# HDMI_INTERFACE.net
KiCad netlist of a schematic drawn in Altium Designer
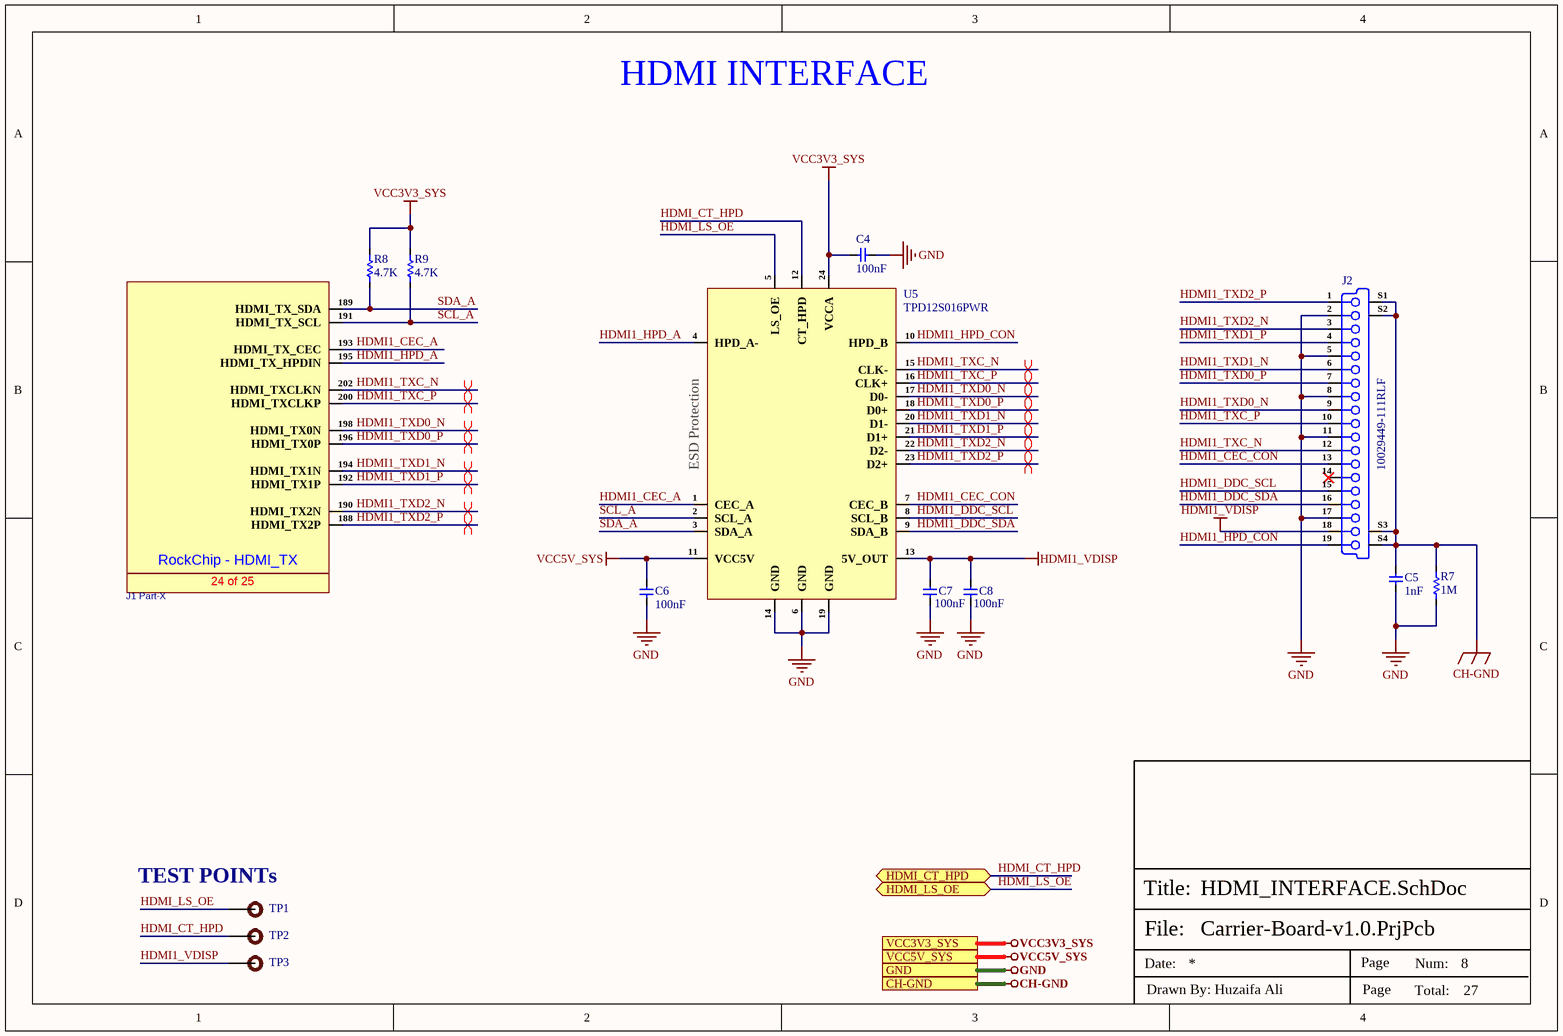
[diagram p0: HDMI_INTERFACE.SchDoc]

(export (version "E")
  (design (tool "Eeschema 10.0.6"))
  (components
    (comp (ref "C4")
      (value "100nF")
      (footprint "Cap-0402")
      (description "CAP CER 0.1UF 16V X5R 0402")
      (fields
        (field (name "MANUFACTURER") "Yageo")
        (field (name "MANUFACTURER PART NUMBER") "CC0402KRX5R7BB104")
      )
      (libsource (lib "eSpark Libraries") (part "CC0402KRX5R7BB104"))
    )
    (comp (ref "C5")
      (value "1nF")
      (footprint "Cap-1206")
      (description "CAP CER 1000PF 2KV X7R 1206")
      (fields
        (field (name "MANUFACTURER") "Yageo")
        (field (name "MANUFACTURER PART NUMBER") "CC1206KKX7RDBB102")
      )
      (libsource (lib "eSpark Libraries") (part "CC1206KKX7RDBB102"))
    )
    (comp (ref "C6")
      (value "100nF")
      (footprint "Cap-0402")
      (description "CAP CER 0.1UF 16V X5R 0402")
      (fields
        (field (name "MANUFACTURER") "Yageo")
        (field (name "MANUFACTURER PART NUMBER") "CC0402KRX5R7BB104")
      )
      (libsource (lib "eSpark Libraries") (part "CC0402KRX5R7BB104"))
    )
    (comp (ref "C7")
      (value "100nF")
      (footprint "Cap-0402")
      (description "CAP CER 0.1UF 16V X5R 0402")
      (fields
        (field (name "MANUFACTURER") "Yageo")
        (field (name "MANUFACTURER PART NUMBER") "CC0402KRX5R7BB104")
      )
      (libsource (lib "eSpark Libraries") (part "CC0402KRX5R7BB104"))
    )
    (comp (ref "C8")
      (value "100nF")
      (footprint "Cap-0402")
      (description "CAP CER 0.1UF 16V X5R 0402")
      (fields
        (field (name "MANUFACTURER") "Yageo")
        (field (name "MANUFACTURER PART NUMBER") "CC0402KRX5R7BB104")
      )
      (libsource (lib "eSpark Libraries") (part "CC0402KRX5R7BB104"))
    )
    (comp (ref "J1 Part-")
      (value "AS0B826-S78B-7H")
      (footprint "AS0B826-S78B-7H")
      (description "SMD,P=0.5mm,Surface Mount，Right Angle")
      (fields (field (name "MANUFACTURER") "FOXCONN") (field (name "LCSC PART NUMBER") "C426232"))
      (libsource (lib "eSpark Libraries") (part "AS0B826-S78B-7H"))
    )
    (comp (ref "J2")
      (value "10029449-111RLF")
      (footprint "10029449-111RLF")
      (description "CONN RCPT 1.4 HDMI 19POS SMD R/A")
      (fields (field (name "MANUFACTURER") "Amphenol ICC / FCI") (field (name "LCSC PART NUMBER") "C427307"))
      (libsource (lib "eSpark Libraries") (part "10029449-111RLF"))
    )
    (comp (ref "R7")
      (value "1M")
      (footprint "Res-0402")
      (description "RES SMD 1M OHM 5% 1/16W 0402")
      (fields
        (field (name "MANUFACTURER") "Yageo")
        (field (name "MANUFACTURER PART NUMBER") "AF0402JR-071ML")
      )
      (libsource (lib "eSpark Libraries") (part "AF0402JR-071ML"))
    )
    (comp (ref "R8")
      (value "4.7K")
      (footprint "Res-0402")
      (description "RES 4.7K OHM 1% 1/16W 0402")
      (fields
        (field (name "MANUFACTURER") "Yageo")
        (field (name "MANUFACTURER PART NUMBER") "RC0402FR-074K7L")
      )
      (libsource (lib "eSpark Libraries") (part "RC0402FR-074K7L"))
    )
    (comp (ref "R9")
      (value "4.7K")
      (footprint "Res-0402")
      (description "RES 4.7K OHM 1% 1/16W 0402")
      (fields
        (field (name "MANUFACTURER") "Yageo")
        (field (name "MANUFACTURER PART NUMBER") "RC0402FR-074K7L")
      )
      (libsource (lib "eSpark Libraries") (part "RC0402FR-074K7L"))
    )
    (comp (ref "TP1")
      (value "TEST POINT 0.5mm Dia")
      (footprint "Test-point - 0.5mm")
      (description "Test Point ON")
      (libsource (lib "eSpark Libraries") (part "TEST POINT 0.5mm Dia"))
    )
    (comp (ref "TP2")
      (value "TEST POINT 0.5mm Dia")
      (footprint "Test-point - 0.5mm")
      (description "Test Point ON")
      (libsource (lib "eSpark Libraries") (part "TEST POINT 0.5mm Dia"))
    )
    (comp (ref "TP3")
      (value "TEST POINT 0.5mm Dia")
      (footprint "Test-point - 0.5mm")
      (description "Test Point ON")
      (libsource (lib "eSpark Libraries") (part "TEST POINT 0.5mm Dia"))
    )
    (comp (ref "U5")
      (value "TPD12S016PWR")
      (footprint "24-TSSOP")
      (description "IC INTERFACE SPECIALIZED 24TSSOP")
      (fields (field (name "MANUFACTURER") "Texas Instruments"))
      (libsource (lib "eSpark Libraries") (part "TPD12S016PWR"))
    )
  )
  (nets
    (net (code "1") (name "/HDMI1_CEC_A") (class "Default")
      (node (ref "J1 Part-") (pin "193") (pinfunction "HDMI_TX_CEC_193") (pintype "passive"))
      (node (ref "U5") (pin "1") (pinfunction "CEC_A_1") (pintype "passive"))
    )
    (net (code "2") (name "/HDMI1_CEC_CON") (class "Default")
      (node (ref "J2") (pin "13") (pintype "passive"))
      (node (ref "U5") (pin "7") (pinfunction "CEC_B_7") (pintype "passive"))
    )
    (net (code "3") (name "/HDMI1_DDC_SCL") (class "Default")
      (node (ref "J2") (pin "15") (pintype "passive"))
      (node (ref "U5") (pin "8") (pinfunction "SCL_B_8") (pintype "passive"))
    )
    (net (code "4") (name "/HDMI1_DDC_SDA") (class "Default")
      (node (ref "J2") (pin "16") (pintype "passive"))
      (node (ref "U5") (pin "9") (pinfunction "SDA_B_9") (pintype "passive"))
    )
    (net (code "5") (name "/HDMI1_HPD_A") (class "Default")
      (node (ref "J1 Part-") (pin "195") (pinfunction "HDMI_TX_HPDIN_195") (pintype "passive"))
      (node (ref "U5") (pin "4") (pinfunction "HPD_A-_4") (pintype "passive"))
    )
    (net (code "6") (name "/HDMI1_HPD_CON") (class "Default")
      (node (ref "J2") (pin "19") (pintype "passive"))
      (node (ref "U5") (pin "10") (pinfunction "HPD_B_10") (pintype "passive"))
    )
    (net (code "7") (name "/HDMI1_TXC_N") (class "Default")
      (node (ref "J1 Part-") (pin "202") (pinfunction "HDMI_TXCLKN_202") (pintype "passive"))
      (node (ref "J2") (pin "12") (pintype "passive"))
      (node (ref "U5") (pin "15") (pinfunction "CLK-_15") (pintype "passive"))
    )
    (net (code "8") (name "/HDMI1_TXC_P") (class "Default")
      (node (ref "J1 Part-") (pin "200") (pinfunction "HDMI_TXCLKP_200") (pintype "passive"))
      (node (ref "J2") (pin "10") (pintype "passive"))
      (node (ref "U5") (pin "16") (pinfunction "CLK+_16") (pintype "passive"))
    )
    (net (code "9") (name "/HDMI1_TXD0_N") (class "Default")
      (node (ref "J1 Part-") (pin "198") (pinfunction "HDMI_TX0N_198") (pintype "passive"))
      (node (ref "J2") (pin "9") (pintype "passive"))
      (node (ref "U5") (pin "17") (pinfunction "D0-_17") (pintype "passive"))
    )
    (net (code "10") (name "/HDMI1_TXD0_P") (class "Default")
      (node (ref "J1 Part-") (pin "196") (pinfunction "HDMI_TX0P_196") (pintype "passive"))
      (node (ref "J2") (pin "7") (pintype "passive"))
      (node (ref "U5") (pin "18") (pinfunction "D0+_18") (pintype "passive"))
    )
    (net (code "11") (name "/HDMI1_TXD1_N") (class "Default")
      (node (ref "J1 Part-") (pin "194") (pinfunction "HDMI_TX1N_194") (pintype "passive"))
      (node (ref "J2") (pin "6") (pintype "passive"))
      (node (ref "U5") (pin "20") (pinfunction "D1-_20") (pintype "passive"))
    )
    (net (code "12") (name "/HDMI1_TXD1_P") (class "Default")
      (node (ref "J1 Part-") (pin "192") (pinfunction "HDMI_TX1P_192") (pintype "passive"))
      (node (ref "J2") (pin "4") (pintype "passive"))
      (node (ref "U5") (pin "21") (pinfunction "D1+_21") (pintype "passive"))
    )
    (net (code "13") (name "/HDMI1_TXD2_N") (class "Default")
      (node (ref "J1 Part-") (pin "190") (pinfunction "HDMI_TX2N_190") (pintype "passive"))
      (node (ref "J2") (pin "3") (pintype "passive"))
      (node (ref "U5") (pin "22") (pinfunction "D2-_22") (pintype "passive"))
    )
    (net (code "14") (name "/HDMI1_TXD2_P") (class "Default")
      (node (ref "J1 Part-") (pin "188") (pinfunction "HDMI_TX2P_188") (pintype "passive"))
      (node (ref "J2") (pin "1") (pintype "passive"))
      (node (ref "U5") (pin "23") (pinfunction "D2+_23") (pintype "passive"))
    )
    (net (code "15") (name "/HDMI_CT_HPD") (class "Default")
      (node (ref "TP2") (pin "1") (pinfunction "1_1") (pintype "passive"))
      (node (ref "U5") (pin "12") (pinfunction "CT_HPD_12") (pintype "passive"))
    )
    (net (code "16") (name "/HDMI_LS_OE") (class "Default")
      (node (ref "TP1") (pin "1") (pinfunction "1_1") (pintype "passive"))
      (node (ref "U5") (pin "5") (pinfunction "LS_OE_5") (pintype "passive"))
    )
    (net (code "17") (name "/SCL_A") (class "Default")
      (node (ref "J1 Part-") (pin "191") (pinfunction "HDMI_TX_SCL_191") (pintype "passive"))
      (node (ref "R9") (pin "2") (pinfunction "2_2") (pintype "passive"))
      (node (ref "U5") (pin "2") (pinfunction "SCL_A_2") (pintype "passive"))
    )
    (net (code "18") (name "/SDA_A") (class "Default")
      (node (ref "J1 Part-") (pin "189") (pinfunction "HDMI_TX_SDA_189") (pintype "passive"))
      (node (ref "R8") (pin "2") (pinfunction "2_2") (pintype "passive"))
      (node (ref "U5") (pin "3") (pinfunction "SDA_A_3") (pintype "passive"))
    )
    (net (code "19") (name "CH-GND") (class "Default")
      (node (ref "C5") (pin "2") (pinfunction "2_2") (pintype "passive"))
      (node (ref "J2") (pin "S1") (pinfunction "Shield_S1") (pintype "passive"))
      (node (ref "J2") (pin "S2") (pinfunction "Shield_S2") (pintype "passive"))
      (node (ref "J2") (pin "S3") (pinfunction "Shield_S3") (pintype "passive"))
      (node (ref "J2") (pin "S4") (pinfunction "Shield_S4") (pintype "passive"))
      (node (ref "R7") (pin "2") (pinfunction "2_2") (pintype "passive"))
    )
    (net (code "20") (name "GND") (class "Default")
      (node (ref "C4") (pin "1") (pinfunction "1_1") (pintype "passive"))
      (node (ref "C5") (pin "1") (pinfunction "1_1") (pintype "passive"))
      (node (ref "C6") (pin "2") (pinfunction "2_2") (pintype "passive"))
      (node (ref "C7") (pin "2") (pinfunction "2_2") (pintype "passive"))
      (node (ref "C8") (pin "2") (pinfunction "2_2") (pintype "passive"))
      (node (ref "J2") (pin "11") (pintype "passive"))
      (node (ref "J2") (pin "17") (pintype "passive"))
      (node (ref "J2") (pin "2") (pintype "passive"))
      (node (ref "J2") (pin "5") (pintype "passive"))
      (node (ref "J2") (pin "8") (pintype "passive"))
      (node (ref "R7") (pin "1") (pinfunction "1_1") (pintype "passive"))
      (node (ref "U5") (pin "14") (pinfunction "GND_14") (pintype "passive"))
      (node (ref "U5") (pin "19") (pinfunction "GND_19") (pintype "passive"))
      (node (ref "U5") (pin "6") (pinfunction "GND_6") (pintype "passive"))
    )
    (net (code "21") (name "HDMI1_VDISP") (class "Default")
      (node (ref "C7") (pin "1") (pinfunction "1_1") (pintype "passive"))
      (node (ref "C8") (pin "1") (pinfunction "1_1") (pintype "passive"))
      (node (ref "J2") (pin "18") (pintype "passive"))
      (node (ref "TP3") (pin "1") (pinfunction "1_1") (pintype "passive"))
      (node (ref "U5") (pin "13") (pinfunction "5V_OUT_13") (pintype "passive"))
    )
    (net (code "22") (name "VCC3V3_SYS") (class "Default")
      (node (ref "C4") (pin "2") (pinfunction "2_2") (pintype "passive"))
      (node (ref "R8") (pin "1") (pinfunction "1_1") (pintype "passive"))
      (node (ref "R9") (pin "1") (pinfunction "1_1") (pintype "passive"))
      (node (ref "U5") (pin "24") (pinfunction "VCCA_24") (pintype "passive"))
    )
    (net (code "23") (name "VCC5V_SYS") (class "Default")
      (node (ref "C6") (pin "1") (pinfunction "1_1") (pintype "passive"))
      (node (ref "U5") (pin "11") (pinfunction "VCC5V_11") (pintype "passive"))
    )
    (net (code "24") (name "unconnected-(J2-Pad14)") (class "Default")
      (node (ref "J2") (pin "14") (pintype "passive+no_connect"))
    )
  )
)
